# darwin-weather-module.net
KiCad netlist of a schematic drawn in EAGLE
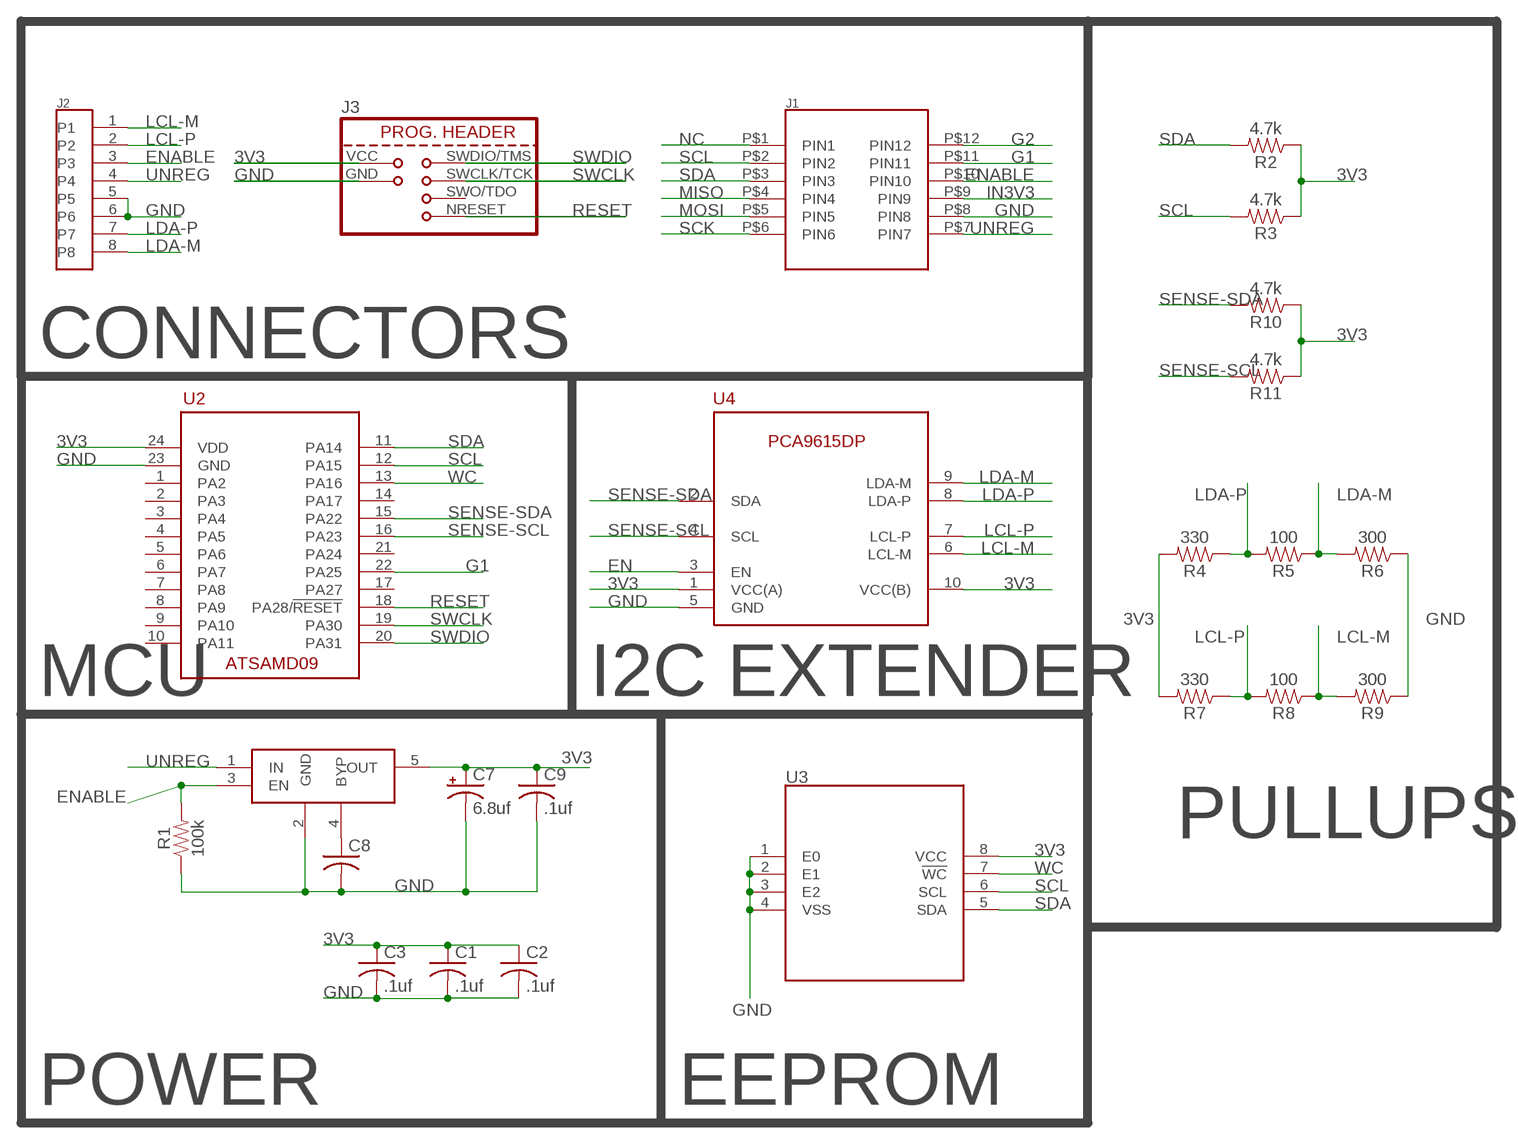
[diagram p0: schematic, sheet 1]

(export (version "E")
  (design (tool "Eeschema 10.0.6"))
  (components
    (comp (ref "C1")
      (value ".1uf")
      (footprint "eagle-import:C0603K")
      (libsource (lib "eagle-import") (part "C-USC0603K"))
    )
    (comp (ref "C2")
      (value ".1uf")
      (footprint "eagle-import:C0603K")
      (libsource (lib "eagle-import") (part "C-USC0603K"))
    )
    (comp (ref "C3")
      (value ".1uf")
      (footprint "eagle-import:C0603K")
      (libsource (lib "eagle-import") (part "C-USC0603K"))
    )
    (comp (ref "C7")
      (value "6.8uf")
      (footprint "eagle-import:A_3216-18R")
      (libsource (lib "eagle-import") (part "CPOL-USA/3216-18R"))
    )
    (comp (ref "C8")
      (value "C-USC0603K")
      (footprint "eagle-import:C0603K")
      (libsource (lib "eagle-import") (part "C-USC0603K"))
    )
    (comp (ref "C9")
      (value ".1uf")
      (footprint "eagle-import:C0603K")
      (libsource (lib "eagle-import") (part "C-USC0603K"))
    )
    (comp (ref "J1")
      (value "2X6-HEADERS")
      (footprint "eagle-import:M20-7810645")
      (libsource (lib "eagle-import") (part "2X6-HEADERS"))
    )
    (comp (ref "J2")
      (value "95501-6889VERT")
      (footprint "eagle-import:85513-5009")
      (libsource (lib "eagle-import") (part "95501-6889VERT"))
    )
    (comp (ref "J3")
      (value "TAG-CONNECT")
      (footprint "eagle-import:TC2030-IDC")
      (libsource (lib "eagle-import") (part "TAG-CONNECT"))
    )
    (comp (ref "R1")
      (value "100k")
      (footprint "eagle-import:0603")
      (libsource (lib "eagle-import") (part "100KOHM-0603-1/10W-1%"))
    )
    (comp (ref "R2")
      (value "4.7k")
      (footprint "eagle-import:0603")
      (libsource (lib "eagle-import") (part "100KOHM-0603-1/10W-1%"))
    )
    (comp (ref "R3")
      (value "4.7k")
      (footprint "eagle-import:0603")
      (libsource (lib "eagle-import") (part "100KOHM-0603-1/10W-1%"))
    )
    (comp (ref "R4")
      (value "330")
      (footprint "eagle-import:0603")
      (libsource (lib "eagle-import") (part "100KOHM-0603-1/10W-1%"))
    )
    (comp (ref "R5")
      (value "100")
      (footprint "eagle-import:0603")
      (libsource (lib "eagle-import") (part "100KOHM-0603-1/10W-1%"))
    )
    (comp (ref "R6")
      (value "300")
      (footprint "eagle-import:0603")
      (libsource (lib "eagle-import") (part "100KOHM-0603-1/10W-1%"))
    )
    (comp (ref "R7")
      (value "330")
      (footprint "eagle-import:0603")
      (libsource (lib "eagle-import") (part "100KOHM-0603-1/10W-1%"))
    )
    (comp (ref "R8")
      (value "100")
      (footprint "eagle-import:0603")
      (libsource (lib "eagle-import") (part "100KOHM-0603-1/10W-1%"))
    )
    (comp (ref "R9")
      (value "300")
      (footprint "eagle-import:0603")
      (libsource (lib "eagle-import") (part "100KOHM-0603-1/10W-1%"))
    )
    (comp (ref "R10")
      (value "4.7k")
      (footprint "eagle-import:0603")
      (libsource (lib "eagle-import") (part "100KOHM-0603-1/10W-1%"))
    )
    (comp (ref "R11")
      (value "4.7k")
      (footprint "eagle-import:0603")
      (libsource (lib "eagle-import") (part "100KOHM-0603-1/10W-1%"))
    )
    (comp (ref "U$4")
      (value "MIC5219-3.3YM5-TR")
      (footprint "eagle-import:SOT95P280X145-5")
      (libsource (lib "eagle-import") (part "MIC5219-3.3YM5-TR"))
    )
    (comp (ref "U2")
      (value "ATSAMD09")
      (footprint "eagle-import:QFN50P400X400X100-25T200")
      (libsource (lib "eagle-import") (part "ATSAMD09"))
    )
    (comp (ref "U3")
      (value "M24C02-WMN6TP")
      (footprint "eagle-import:SOIC127P600X175-8")
      (libsource (lib "eagle-import") (part "M24C02-WMN6TP"))
    )
    (comp (ref "U4")
      (value "PCA9615")
      (footprint "eagle-import:SOP50P490X110-10")
      (libsource (lib "eagle-import") (part "PCA9615"))
    )
  )
  (nets
    (net (code "1") (name "/3V3") (class "Default")
      (node (ref "C1") (pin "1") (pinfunction "1_1") (pintype "passive"))
      (node (ref "C2") (pin "1") (pinfunction "1_1") (pintype "passive"))
      (node (ref "C3") (pin "1") (pinfunction "1_1") (pintype "passive"))
      (node (ref "C7") (pin "+") (pinfunction "+_+") (pintype "passive"))
      (node (ref "C9") (pin "1") (pinfunction "1_1") (pintype "passive"))
      (node (ref "J3") (pin "VCC") (pinfunction "VCC_VCC") (pintype "bidirectional"))
      (node (ref "R10") (pin "1") (pinfunction "1_1") (pintype "passive"))
      (node (ref "R11") (pin "1") (pinfunction "1_1") (pintype "passive"))
      (node (ref "R2") (pin "1") (pinfunction "1_1") (pintype "passive"))
      (node (ref "R3") (pin "1") (pinfunction "1_1") (pintype "passive"))
      (node (ref "R4") (pin "2") (pinfunction "2_2") (pintype "passive"))
      (node (ref "R7") (pin "2") (pinfunction "2_2") (pintype "passive"))
      (node (ref "U$4") (pin "5") (pinfunction "OUT_5") (pintype "bidirectional"))
      (node (ref "U2") (pin "24") (pinfunction "VDD_24") (pintype "bidirectional"))
      (node (ref "U3") (pin "8") (pinfunction "VCC_8") (pintype "bidirectional"))
      (node (ref "U4") (pin "1") (pinfunction "VCC(A)_1") (pintype "bidirectional"))
      (node (ref "U4") (pin "10") (pinfunction "VCC(B)_10") (pintype "bidirectional"))
    )
    (net (code "2") (name "/EN") (class "Default")
      (node (ref "U4") (pin "3") (pinfunction "EN_3") (pintype "bidirectional"))
    )
    (net (code "3") (name "/ENABLE") (class "Default")
      (node (ref "J1") (pin "P$10") (pinfunction "PIN10_P$10") (pintype "bidirectional"))
      (node (ref "J2") (pin "3") (pinfunction "P3_3") (pintype "bidirectional"))
      (node (ref "R1") (pin "2") (pinfunction "2_2") (pintype "passive"))
      (node (ref "U$4") (pin "3") (pinfunction "EN_3") (pintype "bidirectional"))
    )
    (net (code "4") (name "/G1") (class "Default")
      (node (ref "J1") (pin "P$11") (pinfunction "PIN11_P$11") (pintype "bidirectional"))
      (node (ref "U2") (pin "22") (pinfunction "PA25_22") (pintype "bidirectional"))
    )
    (net (code "5") (name "/G2") (class "Default")
      (node (ref "J1") (pin "P$12") (pinfunction "PIN12_P$12") (pintype "bidirectional"))
    )
    (net (code "6") (name "/GND") (class "Default")
      (node (ref "C1") (pin "2") (pinfunction "2_2") (pintype "passive"))
      (node (ref "C2") (pin "2") (pinfunction "2_2") (pintype "passive"))
      (node (ref "C3") (pin "2") (pinfunction "2_2") (pintype "passive"))
      (node (ref "C7") (pin "-") (pinfunction "-_-") (pintype "passive"))
      (node (ref "C8") (pin "2") (pinfunction "2_2") (pintype "passive"))
      (node (ref "C9") (pin "2") (pinfunction "2_2") (pintype "passive"))
      (node (ref "J1") (pin "P$8") (pinfunction "PIN8_P$8") (pintype "bidirectional"))
      (node (ref "J2") (pin "5") (pinfunction "P5_5") (pintype "bidirectional"))
      (node (ref "J2") (pin "6") (pinfunction "P6_6") (pintype "bidirectional"))
      (node (ref "J3") (pin "GND") (pinfunction "GND_GND") (pintype "bidirectional"))
      (node (ref "R1") (pin "1") (pinfunction "1_1") (pintype "passive"))
      (node (ref "R6") (pin "1") (pinfunction "1_1") (pintype "passive"))
      (node (ref "R9") (pin "1") (pinfunction "1_1") (pintype "passive"))
      (node (ref "U$4") (pin "2") (pinfunction "GND_2") (pintype "bidirectional"))
      (node (ref "U2") (pin "23") (pinfunction "GND_23") (pintype "bidirectional"))
      (node (ref "U3") (pin "1") (pinfunction "E0_1") (pintype "bidirectional"))
      (node (ref "U3") (pin "2") (pinfunction "E1_2") (pintype "bidirectional"))
      (node (ref "U3") (pin "3") (pinfunction "E2_3") (pintype "bidirectional"))
      (node (ref "U3") (pin "4") (pinfunction "VSS_4") (pintype "bidirectional"))
      (node (ref "U4") (pin "5") (pinfunction "GND_5") (pintype "bidirectional"))
    )
    (net (code "7") (name "/IN3V3") (class "Default")
      (node (ref "J1") (pin "P$9") (pinfunction "PIN9_P$9") (pintype "bidirectional"))
    )
    (net (code "8") (name "/LCL-M") (class "Default")
      (node (ref "J2") (pin "1") (pinfunction "P1_1") (pintype "bidirectional"))
      (node (ref "R8") (pin "1") (pinfunction "1_1") (pintype "passive"))
      (node (ref "R9") (pin "2") (pinfunction "2_2") (pintype "passive"))
      (node (ref "U4") (pin "6") (pinfunction "LCL-M_6") (pintype "bidirectional"))
    )
    (net (code "9") (name "/LCL-P") (class "Default")
      (node (ref "J2") (pin "2") (pinfunction "P2_2") (pintype "bidirectional"))
      (node (ref "R7") (pin "1") (pinfunction "1_1") (pintype "passive"))
      (node (ref "R8") (pin "2") (pinfunction "2_2") (pintype "passive"))
      (node (ref "U4") (pin "7") (pinfunction "LCL-P_7") (pintype "bidirectional"))
    )
    (net (code "10") (name "/LDA-M") (class "Default")
      (node (ref "J2") (pin "8") (pinfunction "P8_8") (pintype "bidirectional"))
      (node (ref "R5") (pin "1") (pinfunction "1_1") (pintype "passive"))
      (node (ref "R6") (pin "2") (pinfunction "2_2") (pintype "passive"))
      (node (ref "U4") (pin "9") (pinfunction "LDA-M_9") (pintype "bidirectional"))
    )
    (net (code "11") (name "/LDA-P") (class "Default")
      (node (ref "J2") (pin "7") (pinfunction "P7_7") (pintype "bidirectional"))
      (node (ref "R4") (pin "1") (pinfunction "1_1") (pintype "passive"))
      (node (ref "R5") (pin "2") (pinfunction "2_2") (pintype "passive"))
      (node (ref "U4") (pin "8") (pinfunction "LDA-P_8") (pintype "bidirectional"))
    )
    (net (code "12") (name "/MISO") (class "Default")
      (node (ref "J1") (pin "P$4") (pinfunction "PIN4_P$4") (pintype "bidirectional"))
    )
    (net (code "13") (name "/MOSI") (class "Default")
      (node (ref "J1") (pin "P$5") (pinfunction "PIN5_P$5") (pintype "bidirectional"))
    )
    (net (code "14") (name "/NC") (class "Default")
      (node (ref "J1") (pin "P$1") (pinfunction "PIN1_P$1") (pintype "bidirectional"))
    )
    (net (code "15") (name "/RESET") (class "Default")
      (node (ref "J3") (pin "NRESET") (pinfunction "RESET_NRESET") (pintype "bidirectional"))
      (node (ref "U2") (pin "18") (pinfunction "PA28/~{RESET}_18") (pintype "bidirectional"))
    )
    (net (code "16") (name "/SCK") (class "Default")
      (node (ref "J1") (pin "P$6") (pinfunction "PIN6_P$6") (pintype "bidirectional"))
    )
    (net (code "17") (name "/SCL") (class "Default")
      (node (ref "J1") (pin "P$2") (pinfunction "PIN2_P$2") (pintype "bidirectional"))
      (node (ref "R3") (pin "2") (pinfunction "2_2") (pintype "passive"))
      (node (ref "U2") (pin "12") (pinfunction "PA15_12") (pintype "bidirectional"))
      (node (ref "U3") (pin "6") (pinfunction "SCL_6") (pintype "bidirectional"))
    )
    (net (code "18") (name "/SDA") (class "Default")
      (node (ref "J1") (pin "P$3") (pinfunction "PIN3_P$3") (pintype "bidirectional"))
      (node (ref "R2") (pin "2") (pinfunction "2_2") (pintype "passive"))
      (node (ref "U2") (pin "11") (pinfunction "PA14_11") (pintype "bidirectional"))
      (node (ref "U3") (pin "5") (pinfunction "SDA_5") (pintype "bidirectional"))
    )
    (net (code "19") (name "/SENSE-SCL") (class "Default")
      (node (ref "R11") (pin "2") (pinfunction "2_2") (pintype "passive"))
      (node (ref "U2") (pin "16") (pinfunction "PA23_16") (pintype "bidirectional"))
      (node (ref "U4") (pin "4") (pinfunction "SCL_4") (pintype "bidirectional"))
    )
    (net (code "20") (name "/SENSE-SDA") (class "Default")
      (node (ref "R10") (pin "2") (pinfunction "2_2") (pintype "passive"))
      (node (ref "U2") (pin "15") (pinfunction "PA22_15") (pintype "bidirectional"))
      (node (ref "U4") (pin "2") (pinfunction "SDA_2") (pintype "bidirectional"))
    )
    (net (code "21") (name "/SWCLK") (class "Default")
      (node (ref "J3") (pin "SWCLK/TCK") (pinfunction "SWCLK_SWCLK/TCK") (pintype "bidirectional"))
      (node (ref "U2") (pin "19") (pinfunction "PA30_19") (pintype "bidirectional"))
    )
    (net (code "22") (name "/SWDIO") (class "Default")
      (node (ref "J3") (pin "SWDIO/TMS") (pinfunction "SWDIO_SWDIO/TMS") (pintype "bidirectional"))
      (node (ref "U2") (pin "20") (pinfunction "PA31_20") (pintype "bidirectional"))
    )
    (net (code "23") (name "/UNREG") (class "Default")
      (node (ref "J1") (pin "P$7") (pinfunction "PIN7_P$7") (pintype "bidirectional"))
      (node (ref "J2") (pin "4") (pinfunction "P4_4") (pintype "bidirectional"))
      (node (ref "U$4") (pin "1") (pinfunction "IN_1") (pintype "bidirectional"))
    )
    (net (code "24") (name "/WC") (class "Default")
      (node (ref "U2") (pin "13") (pinfunction "PA16_13") (pintype "bidirectional"))
      (node (ref "U3") (pin "7") (pinfunction "~{WC}_7") (pintype "bidirectional"))
    )
    (net (code "25") (name "Net-(U$4-BYP)") (class "Default")
      (node (ref "C8") (pin "1") (pinfunction "1_1") (pintype "passive"))
      (node (ref "U$4") (pin "4") (pinfunction "BYP_4") (pintype "bidirectional"))
    )
    (net (code "26") (name "unconnected-(J3-SWO-PadSWO{slash}TDO)") (class "Default")
      (node (ref "J3") (pin "SWO/TDO") (pinfunction "SWO_SWO/TDO") (pintype "bidirectional"))
    )
    (net (code "27") (name "unconnected-(U2-PA2-Pad1)") (class "Default")
      (node (ref "U2") (pin "1") (pinfunction "PA2_1") (pintype "bidirectional"))
    )
    (net (code "28") (name "unconnected-(U2-PA3-Pad2)") (class "Default")
      (node (ref "U2") (pin "2") (pinfunction "PA3_2") (pintype "bidirectional"))
    )
    (net (code "29") (name "unconnected-(U2-PA4-Pad3)") (class "Default")
      (node (ref "U2") (pin "3") (pinfunction "PA4_3") (pintype "bidirectional"))
    )
    (net (code "30") (name "unconnected-(U2-PA5-Pad4)") (class "Default")
      (node (ref "U2") (pin "4") (pinfunction "PA5_4") (pintype "bidirectional"))
    )
    (net (code "31") (name "unconnected-(U2-PA6-Pad5)") (class "Default")
      (node (ref "U2") (pin "5") (pinfunction "PA6_5") (pintype "bidirectional"))
    )
    (net (code "32") (name "unconnected-(U2-PA7-Pad6)") (class "Default")
      (node (ref "U2") (pin "6") (pinfunction "PA7_6") (pintype "bidirectional"))
    )
    (net (code "33") (name "unconnected-(U2-PA8-Pad7)") (class "Default")
      (node (ref "U2") (pin "7") (pinfunction "PA8_7") (pintype "bidirectional"))
    )
    (net (code "34") (name "unconnected-(U2-PA9-Pad8)") (class "Default")
      (node (ref "U2") (pin "8") (pinfunction "PA9_8") (pintype "bidirectional"))
    )
    (net (code "35") (name "unconnected-(U2-PA10-Pad9)") (class "Default")
      (node (ref "U2") (pin "9") (pinfunction "PA10_9") (pintype "bidirectional"))
    )
    (net (code "36") (name "unconnected-(U2-PA11-Pad10)") (class "Default")
      (node (ref "U2") (pin "10") (pinfunction "PA11_10") (pintype "bidirectional"))
    )
    (net (code "37") (name "unconnected-(U2-PA17-Pad14)") (class "Default")
      (node (ref "U2") (pin "14") (pinfunction "PA17_14") (pintype "bidirectional"))
    )
    (net (code "38") (name "unconnected-(U2-PA24-Pad21)") (class "Default")
      (node (ref "U2") (pin "21") (pinfunction "PA24_21") (pintype "bidirectional"))
    )
    (net (code "39") (name "unconnected-(U2-PA27-Pad17)") (class "Default")
      (node (ref "U2") (pin "17") (pinfunction "PA27_17") (pintype "bidirectional"))
    )
  )
)
